# HEARING_AID.net
KiCad netlist of a schematic drawn in EAGLE
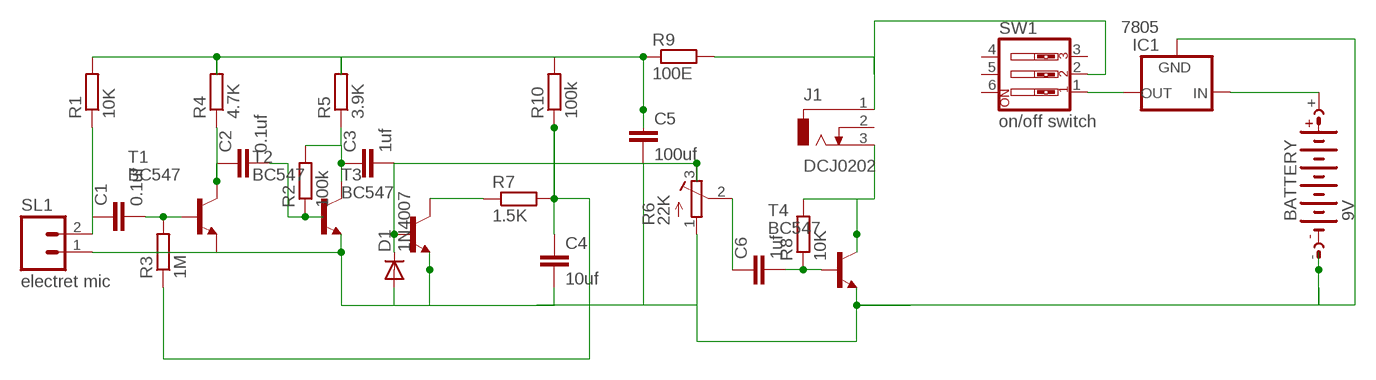
[diagram p0: schematic, sheet 1]

(export (version "E")
  (design (tool "Eeschema 10.0.6"))
  (components
    (comp (ref "BATTERY")
      (value "9V")
      (footprint "eagle-import:AB9V")
      (libsource (lib "eagle-import") (part "AB9V"))
    )
    (comp (ref "C1")
      (value "0.1uf")
      (footprint "eagle-import:C2.5-6")
      (libsource (lib "eagle-import") (part "C2.5/6"))
    )
    (comp (ref "C2")
      (value "0.1uf")
      (footprint "eagle-import:C2.5-6")
      (libsource (lib "eagle-import") (part "C2.5/6"))
    )
    (comp (ref "C3")
      (value "1uf")
      (footprint "eagle-import:C2.5-6")
      (libsource (lib "eagle-import") (part "C2.5/6"))
    )
    (comp (ref "C4")
      (value "10uf")
      (footprint "eagle-import:C2.5-6")
      (libsource (lib "eagle-import") (part "C2.5/6"))
    )
    (comp (ref "C5")
      (value "100uf")
      (footprint "eagle-import:C2.5-6")
      (libsource (lib "eagle-import") (part "C2.5/6"))
    )
    (comp (ref "C6")
      (value "1uf")
      (footprint "eagle-import:C2.5-6")
      (libsource (lib "eagle-import") (part "C2.5/6"))
    )
    (comp (ref "D1")
      (value "1N4007")
      (footprint "eagle-import:DO41-10")
      (libsource (lib "eagle-import") (part "1N4004"))
    )
    (comp (ref "IC1")
      (value "7805")
      (footprint "eagle-import:78XXL")
      (libsource (lib "eagle-import") (part "78XXL"))
    )
    (comp (ref "J1")
      (value "DCJ0202")
      (footprint "eagle-import:DCJ0202")
      (libsource (lib "eagle-import") (part "DCJ0202"))
    )
    (comp (ref "R1")
      (value "10K")
      (footprint "eagle-import:0204_7")
      (libsource (lib "eagle-import") (part "R-EU_0204/7"))
    )
    (comp (ref "R2")
      (value "100k")
      (footprint "eagle-import:0204_7")
      (libsource (lib "eagle-import") (part "R-EU_0204/7"))
    )
    (comp (ref "R3")
      (value "1M")
      (footprint "eagle-import:0204_7")
      (libsource (lib "eagle-import") (part "R-EU_0204/7"))
    )
    (comp (ref "R4")
      (value "4.7K")
      (footprint "eagle-import:0204_7")
      (libsource (lib "eagle-import") (part "R-EU_0204/7"))
    )
    (comp (ref "R5")
      (value "3.9K")
      (footprint "eagle-import:0204_7")
      (libsource (lib "eagle-import") (part "R-EU_0204/7"))
    )
    (comp (ref "R6")
      (value "22K")
      (footprint "eagle-import:RTRIM64P")
      (libsource (lib "eagle-import") (part "R-TRIMM64P"))
    )
    (comp (ref "R7")
      (value "1.5K")
      (footprint "eagle-import:0204_7")
      (libsource (lib "eagle-import") (part "R-EU_0204/7"))
    )
    (comp (ref "R8")
      (value "10K")
      (footprint "eagle-import:0204_7")
      (libsource (lib "eagle-import") (part "R-EU_0204/7"))
    )
    (comp (ref "R9")
      (value "100E")
      (footprint "eagle-import:0204_7")
      (libsource (lib "eagle-import") (part "R-EU_0204/7"))
    )
    (comp (ref "R10")
      (value "100k")
      (footprint "eagle-import:0204_7")
      (libsource (lib "eagle-import") (part "R-EU_0204/7"))
    )
    (comp (ref "SL1")
      (value "electret mic")
      (footprint "eagle-import:02P")
      (libsource (lib "eagle-import") (part "M02"))
    )
    (comp (ref "SW1")
      (value "on/off switch")
      (footprint "eagle-import:EDG-03")
      (libsource (lib "eagle-import") (part "SW_DIP-3"))
    )
    (comp (ref "T1")
      (value "BC547")
      (footprint "eagle-import:TO92")
      (libsource (lib "eagle-import") (part "BC547"))
    )
    (comp (ref "T2")
      (value "BC547")
      (footprint "eagle-import:TO92")
      (libsource (lib "eagle-import") (part "BC547"))
    )
    (comp (ref "T3")
      (value "BC547")
      (footprint "eagle-import:TO92")
      (libsource (lib "eagle-import") (part "BC547"))
    )
    (comp (ref "T4")
      (value "BC547")
      (footprint "eagle-import:TO92")
      (libsource (lib "eagle-import") (part "BC547"))
    )
  )
  (nets
    (net (code "1") (name "Net-(BATTERY-Pad+)") (class "Default")
      (node (ref "BATTERY") (pin "+") (pinfunction "+_+") (pintype "passive"))
      (node (ref "IC1") (pin "IN") (pinfunction "IN_IN") (pintype "input"))
    )
    (net (code "2") (name "Net-(C1-Pad1)") (class "Default")
      (node (ref "C1") (pin "1") (pinfunction "1_1") (pintype "passive"))
      (node (ref "R1") (pin "1") (pinfunction "1_1") (pintype "passive"))
      (node (ref "SL1") (pin "2") (pinfunction "2_2") (pintype "passive"))
    )
    (net (code "3") (name "Net-(C4-Pad1)") (class "Default")
      (node (ref "C4") (pin "1") (pinfunction "1_1") (pintype "passive"))
      (node (ref "R10") (pin "1") (pinfunction "1_1") (pintype "passive"))
      (node (ref "R3") (pin "1") (pinfunction "1_1") (pintype "passive"))
      (node (ref "R7") (pin "2") (pinfunction "2_2") (pintype "passive"))
    )
    (net (code "4") (name "Net-(C5-Pad1)") (class "Default")
      (node (ref "C5") (pin "1") (pinfunction "1_1") (pintype "passive"))
      (node (ref "R1") (pin "2") (pinfunction "2_2") (pintype "passive"))
      (node (ref "R10") (pin "2") (pinfunction "2_2") (pintype "passive"))
      (node (ref "R4") (pin "2") (pinfunction "2_2") (pintype "passive"))
      (node (ref "R5") (pin "2") (pinfunction "2_2") (pintype "passive"))
      (node (ref "R9") (pin "1") (pinfunction "1_1") (pintype "passive"))
    )
    (net (code "5") (name "Net-(IC1-PadOUT)") (class "Default")
      (node (ref "IC1") (pin "OUT") (pinfunction "OUT_OUT") (pintype "passive"))
      (node (ref "SW1") (pin "1") (pinfunction "1_1") (pintype "passive"))
    )
    (net (code "6") (name "Net-(J1-Pad1)") (class "Default")
      (node (ref "J1") (pin "1") (pinfunction "1_1") (pintype "passive"))
      (node (ref "R9") (pin "2") (pinfunction "2_2") (pintype "passive"))
      (node (ref "SW1") (pin "2") (pinfunction "2_2") (pintype "passive"))
    )
    (net (code "7") (name "Net-(R6-A)") (class "Default")
      (node (ref "C3") (pin "2") (pinfunction "2_2") (pintype "passive"))
      (node (ref "D1") (pin "C") (pinfunction "C_C") (pintype "passive"))
      (node (ref "R6") (pin "3") (pinfunction "A_3") (pintype "passive"))
      (node (ref "T3") (pin "2") (pinfunction "B_2") (pintype "passive"))
    )
    (net (code "8") (name "Net-(R6-E)") (class "Default")
      (node (ref "BATTERY") (pin "-") (pinfunction "-_-") (pintype "passive"))
      (node (ref "C4") (pin "2") (pinfunction "2_2") (pintype "passive"))
      (node (ref "C5") (pin "2") (pinfunction "2_2") (pintype "passive"))
      (node (ref "D1") (pin "A") (pinfunction "A_A") (pintype "passive"))
      (node (ref "IC1") (pin "GND") (pinfunction "GND_GND") (pintype "input"))
      (node (ref "R6") (pin "1") (pinfunction "E_1") (pintype "passive"))
      (node (ref "SL1") (pin "1") (pinfunction "1_1") (pintype "passive"))
      (node (ref "T1") (pin "1") (pinfunction "E_1") (pintype "passive"))
      (node (ref "T2") (pin "1") (pinfunction "E_1") (pintype "passive"))
      (node (ref "T3") (pin "1") (pinfunction "E_1") (pintype "passive"))
      (node (ref "T4") (pin "1") (pinfunction "E_1") (pintype "passive"))
    )
    (net (code "9") (name "Net-(R6-S)") (class "Default")
      (node (ref "C6") (pin "1") (pinfunction "1_1") (pintype "passive"))
      (node (ref "R6") (pin "2") (pinfunction "S_2") (pintype "passive"))
    )
    (net (code "10") (name "Net-(T1-B)") (class "Default")
      (node (ref "C1") (pin "2") (pinfunction "2_2") (pintype "passive"))
      (node (ref "R3") (pin "2") (pinfunction "2_2") (pintype "passive"))
      (node (ref "T1") (pin "2") (pinfunction "B_2") (pintype "passive"))
    )
    (net (code "11") (name "Net-(T1-C)") (class "Default")
      (node (ref "C2") (pin "1") (pinfunction "1_1") (pintype "passive"))
      (node (ref "R4") (pin "1") (pinfunction "1_1") (pintype "passive"))
      (node (ref "T1") (pin "3") (pinfunction "C_3") (pintype "passive"))
    )
    (net (code "12") (name "Net-(T2-B)") (class "Default")
      (node (ref "C2") (pin "2") (pinfunction "2_2") (pintype "passive"))
      (node (ref "R2") (pin "1") (pinfunction "1_1") (pintype "passive"))
      (node (ref "T2") (pin "2") (pinfunction "B_2") (pintype "passive"))
    )
    (net (code "13") (name "Net-(T2-C)") (class "Default")
      (node (ref "C3") (pin "1") (pinfunction "1_1") (pintype "passive"))
      (node (ref "R2") (pin "2") (pinfunction "2_2") (pintype "passive"))
      (node (ref "R5") (pin "1") (pinfunction "1_1") (pintype "passive"))
      (node (ref "T2") (pin "3") (pinfunction "C_3") (pintype "passive"))
    )
    (net (code "14") (name "Net-(T3-C)") (class "Default")
      (node (ref "R7") (pin "1") (pinfunction "1_1") (pintype "passive"))
      (node (ref "T3") (pin "3") (pinfunction "C_3") (pintype "passive"))
    )
    (net (code "15") (name "Net-(T4-B)") (class "Default")
      (node (ref "C6") (pin "2") (pinfunction "2_2") (pintype "passive"))
      (node (ref "R8") (pin "1") (pinfunction "1_1") (pintype "passive"))
      (node (ref "T4") (pin "2") (pinfunction "B_2") (pintype "passive"))
    )
    (net (code "16") (name "Net-(T4-C)") (class "Default")
      (node (ref "J1") (pin "3") (pinfunction "3_3") (pintype "passive"))
      (node (ref "R8") (pin "2") (pinfunction "2_2") (pintype "passive"))
      (node (ref "T4") (pin "3") (pinfunction "C_3") (pintype "passive"))
    )
    (net (code "17") (name "unconnected-(J1-Pad2)") (class "Default")
      (node (ref "J1") (pin "2") (pinfunction "2_2") (pintype "passive"))
    )
    (net (code "18") (name "unconnected-(SW1-Pad3)") (class "Default")
      (node (ref "SW1") (pin "3") (pinfunction "3_3") (pintype "passive"))
    )
    (net (code "19") (name "unconnected-(SW1-Pad4)") (class "Default")
      (node (ref "SW1") (pin "4") (pinfunction "4_4") (pintype "passive"))
    )
    (net (code "20") (name "unconnected-(SW1-Pad5)") (class "Default")
      (node (ref "SW1") (pin "5") (pinfunction "5_5") (pintype "passive"))
    )
    (net (code "21") (name "unconnected-(SW1-Pad6)") (class "Default")
      (node (ref "SW1") (pin "6") (pinfunction "6_6") (pintype "passive"))
    )
  )
)
